# TheSixthSense.net
KiCad netlist of a schematic drawn in EAGLE
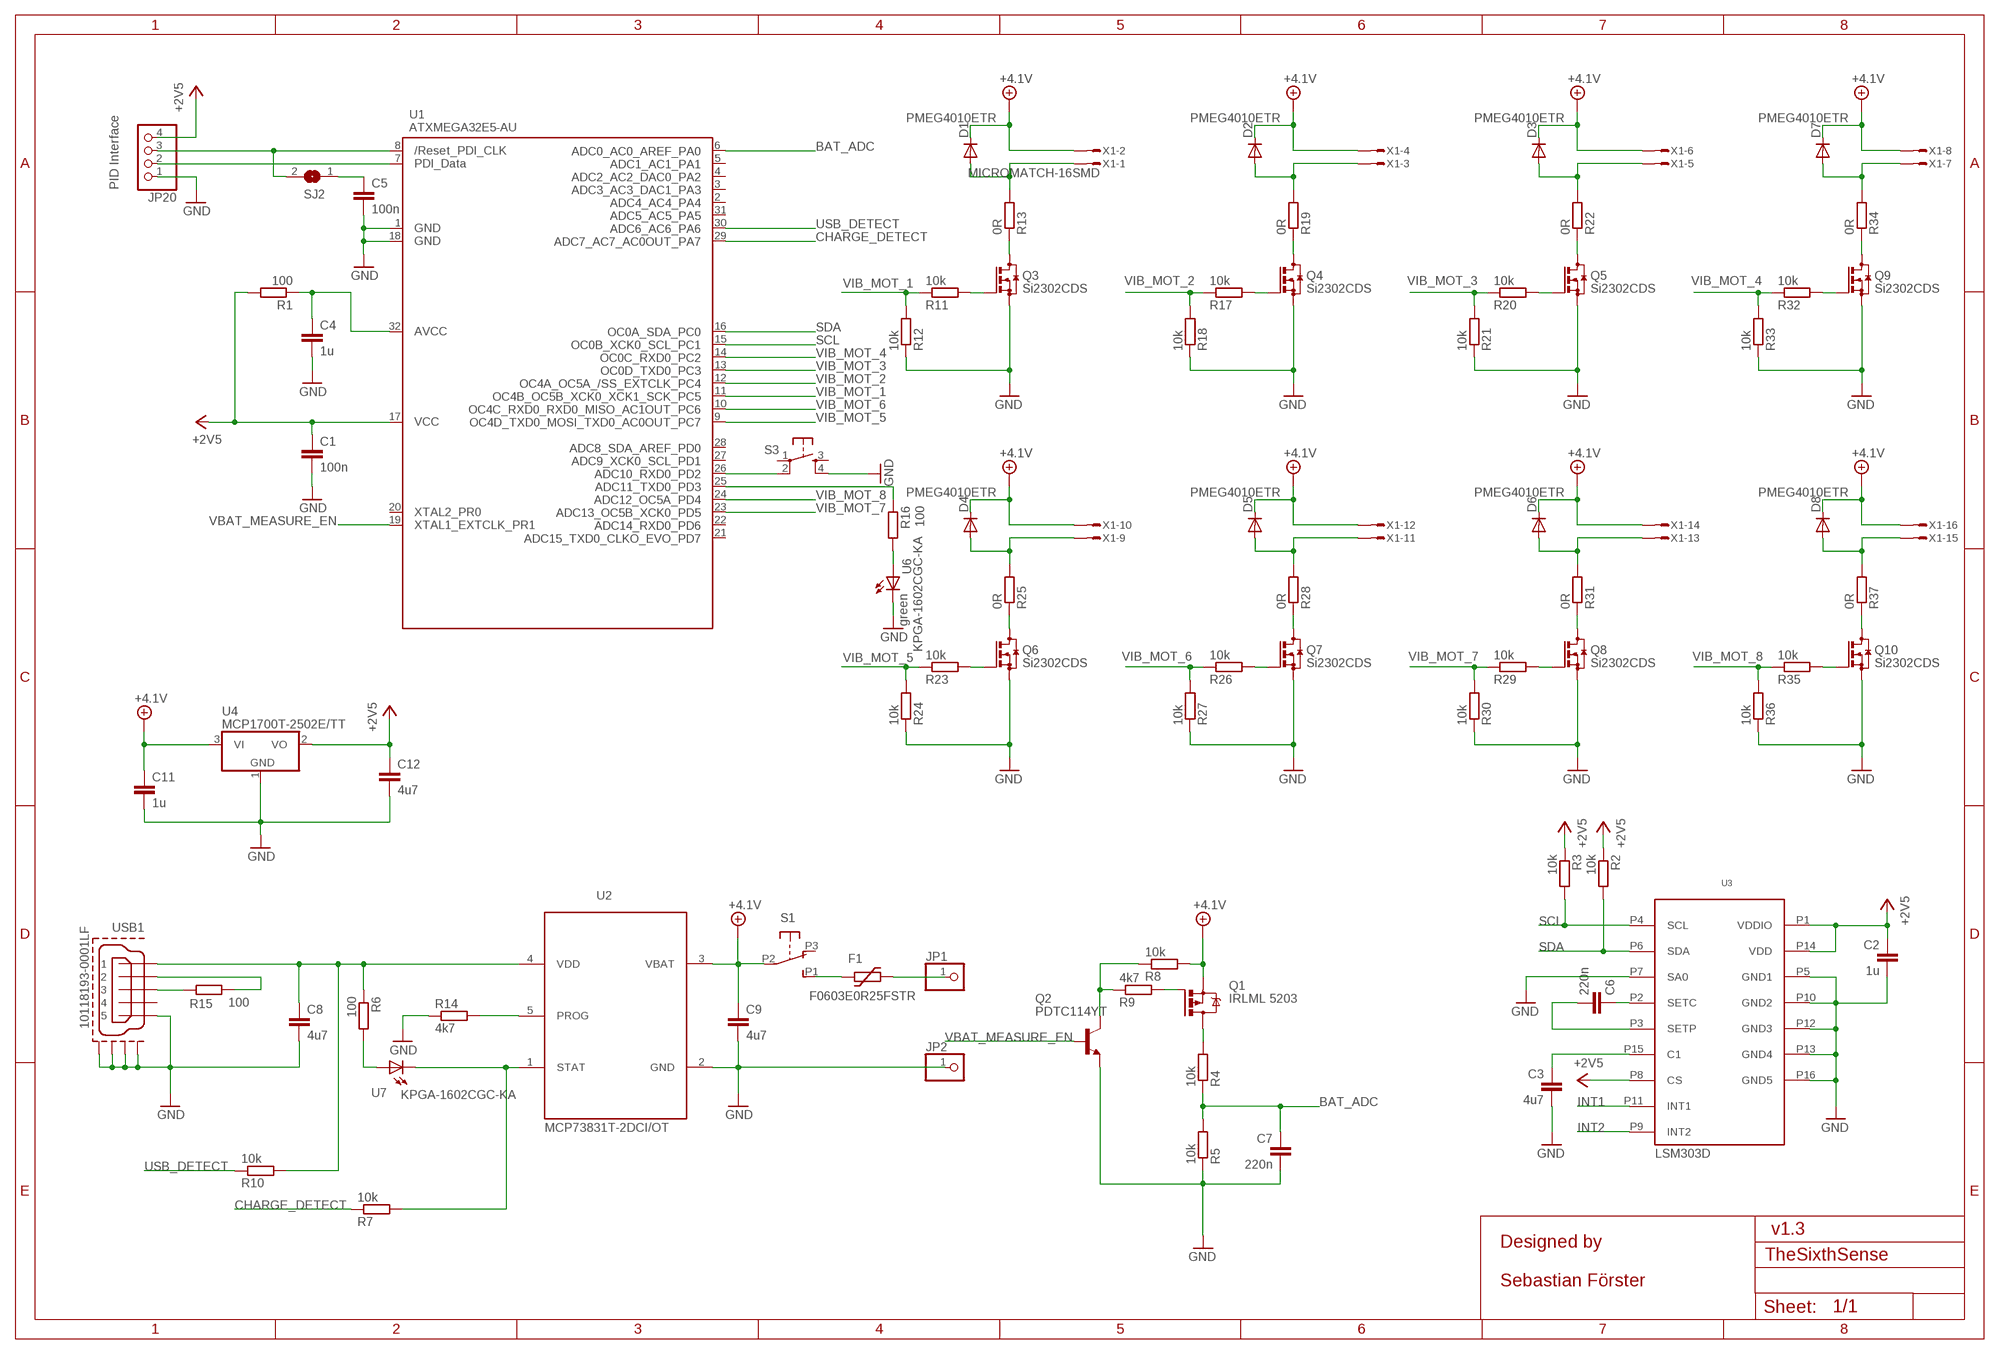
[diagram p0: schematic, sheet 1]

(export (version "E")
  (design (tool "Eeschema 10.0.6"))
  (components
    (comp (ref "C1")
      (value "100n")
      (footprint "eagle-import:C0603")
      (libsource (lib "eagle-import") (part "C-EUC0603"))
    )
    (comp (ref "C2")
      (value "1u")
      (footprint "eagle-import:C0603")
      (libsource (lib "eagle-import") (part "C-EUC0603"))
    )
    (comp (ref "C3")
      (value "4u7")
      (footprint "eagle-import:C0603")
      (libsource (lib "eagle-import") (part "C-EUC0603"))
    )
    (comp (ref "C4")
      (value "1u")
      (footprint "eagle-import:C0603")
      (libsource (lib "eagle-import") (part "C-EUC0603"))
    )
    (comp (ref "C5")
      (value "100n")
      (footprint "eagle-import:C0603")
      (libsource (lib "eagle-import") (part "C-EUC0603"))
    )
    (comp (ref "C6")
      (value "220n")
      (footprint "eagle-import:C0603")
      (libsource (lib "eagle-import") (part "C-EUC0603"))
    )
    (comp (ref "C7")
      (value "220n")
      (footprint "eagle-import:C0603")
      (libsource (lib "eagle-import") (part "C-EUC0603"))
    )
    (comp (ref "C8")
      (value "4u7")
      (footprint "eagle-import:C0603")
      (libsource (lib "eagle-import") (part "C-EUC0603"))
    )
    (comp (ref "C9")
      (value "4u7")
      (footprint "eagle-import:C0603")
      (libsource (lib "eagle-import") (part "C-EUC0603"))
    )
    (comp (ref "C11")
      (value "1u")
      (footprint "eagle-import:C0603")
      (libsource (lib "eagle-import") (part "C-EUC0603"))
    )
    (comp (ref "C12")
      (value "4u7")
      (footprint "eagle-import:C0603")
      (libsource (lib "eagle-import") (part "C-EUC0603"))
    )
    (comp (ref "D1")
      (value "PMEG4010ETR")
      (footprint "eagle-import:SOD123")
      (libsource (lib "eagle-import") (part "MBR0520LT"))
    )
    (comp (ref "D2")
      (value "PMEG4010ETR")
      (footprint "eagle-import:SOD123")
      (libsource (lib "eagle-import") (part "MBR0520LT"))
    )
    (comp (ref "D3")
      (value "PMEG4010ETR")
      (footprint "eagle-import:SOD123")
      (libsource (lib "eagle-import") (part "MBR0520LT"))
    )
    (comp (ref "D4")
      (value "PMEG4010ETR")
      (footprint "eagle-import:SOD123")
      (libsource (lib "eagle-import") (part "MBR0520LT"))
    )
    (comp (ref "D5")
      (value "PMEG4010ETR")
      (footprint "eagle-import:SOD123")
      (libsource (lib "eagle-import") (part "MBR0520LT"))
    )
    (comp (ref "D6")
      (value "PMEG4010ETR")
      (footprint "eagle-import:SOD123")
      (libsource (lib "eagle-import") (part "MBR0520LT"))
    )
    (comp (ref "D7")
      (value "PMEG4010ETR")
      (footprint "eagle-import:SOD123")
      (libsource (lib "eagle-import") (part "MBR0520LT"))
    )
    (comp (ref "D8")
      (value "PMEG4010ETR")
      (footprint "eagle-import:SOD123")
      (libsource (lib "eagle-import") (part "MBR0520LT"))
    )
    (comp (ref "F1")
      (value "F0603E0R25FSTR")
      (footprint "eagle-import:R0603")
      (libsource (lib "eagle-import") (part "PMS1812"))
    )
    (comp (ref "JP1")
      (value "PINHD-1X1")
      (footprint "eagle-import:1X01")
      (libsource (lib "eagle-import") (part "PINHD-1X1"))
    )
    (comp (ref "JP2")
      (value "PINHD-1X1")
      (footprint "eagle-import:1X01")
      (libsource (lib "eagle-import") (part "PINHD-1X1"))
    )
    (comp (ref "JP20")
      (value "PINHD-1X4_2.00")
      (footprint "eagle-import:1X04M")
      (libsource (lib "eagle-import") (part "PINHD-1X4_2.00"))
    )
    (comp (ref "Q1")
      (value "IRLML 5203")
      (footprint "eagle-import:MICRO3")
      (libsource (lib "eagle-import") (part "IRLML5203"))
    )
    (comp (ref "Q2")
      (value "PDTC114YT")
      (footprint "eagle-import:SOT23")
      (libsource (lib "eagle-import") (part "BC848SMDALT1"))
    )
    (comp (ref "Q3")
      (value "Si2302CDS")
      (footprint "eagle-import:SOT23")
      (libsource (lib "eagle-import") (part "BSS123"))
    )
    (comp (ref "Q4")
      (value "Si2302CDS")
      (footprint "eagle-import:SOT23")
      (libsource (lib "eagle-import") (part "BSS123"))
    )
    (comp (ref "Q5")
      (value "Si2302CDS")
      (footprint "eagle-import:SOT23")
      (libsource (lib "eagle-import") (part "BSS123"))
    )
    (comp (ref "Q6")
      (value "Si2302CDS")
      (footprint "eagle-import:SOT23")
      (libsource (lib "eagle-import") (part "BSS123"))
    )
    (comp (ref "Q7")
      (value "Si2302CDS")
      (footprint "eagle-import:SOT23")
      (libsource (lib "eagle-import") (part "BSS123"))
    )
    (comp (ref "Q8")
      (value "Si2302CDS")
      (footprint "eagle-import:SOT23")
      (libsource (lib "eagle-import") (part "BSS123"))
    )
    (comp (ref "Q9")
      (value "Si2302CDS")
      (footprint "eagle-import:SOT23")
      (libsource (lib "eagle-import") (part "BSS123"))
    )
    (comp (ref "Q10")
      (value "Si2302CDS")
      (footprint "eagle-import:SOT23")
      (libsource (lib "eagle-import") (part "BSS123"))
    )
    (comp (ref "R1")
      (value "100")
      (footprint "eagle-import:R0603")
      (libsource (lib "eagle-import") (part "R-EU_R0603"))
    )
    (comp (ref "R2")
      (value "10k")
      (footprint "eagle-import:R0603")
      (libsource (lib "eagle-import") (part "R-EU_R0603"))
    )
    (comp (ref "R3")
      (value "10k")
      (footprint "eagle-import:R0603")
      (libsource (lib "eagle-import") (part "R-EU_R0603"))
    )
    (comp (ref "R4")
      (value "10k")
      (footprint "eagle-import:R0603")
      (libsource (lib "eagle-import") (part "R-EU_R0603"))
    )
    (comp (ref "R5")
      (value "10k")
      (footprint "eagle-import:R0603")
      (libsource (lib "eagle-import") (part "R-EU_R0603"))
    )
    (comp (ref "R6")
      (value "100")
      (footprint "eagle-import:R0603")
      (libsource (lib "eagle-import") (part "R-EU_R0603"))
    )
    (comp (ref "R7")
      (value "10k")
      (footprint "eagle-import:R0603")
      (libsource (lib "eagle-import") (part "R-EU_R0603"))
    )
    (comp (ref "R8")
      (value "10k")
      (footprint "eagle-import:R0603")
      (libsource (lib "eagle-import") (part "R-EU_R0603"))
    )
    (comp (ref "R9")
      (value "4k7")
      (footprint "eagle-import:R0603")
      (libsource (lib "eagle-import") (part "R-EU_R0603"))
    )
    (comp (ref "R10")
      (value "10k")
      (footprint "eagle-import:R0603")
      (libsource (lib "eagle-import") (part "R-EU_R0603"))
    )
    (comp (ref "R11")
      (value "10k")
      (footprint "eagle-import:R0603")
      (libsource (lib "eagle-import") (part "R-EU_R0603"))
    )
    (comp (ref "R12")
      (value "10k")
      (footprint "eagle-import:R0603")
      (libsource (lib "eagle-import") (part "R-EU_R0603"))
    )
    (comp (ref "R13")
      (value "0R")
      (footprint "eagle-import:R0603")
      (libsource (lib "eagle-import") (part "R-EU_R0603"))
    )
    (comp (ref "R14")
      (value "4k7")
      (footprint "eagle-import:R0603")
      (libsource (lib "eagle-import") (part "R-EU_R0603"))
    )
    (comp (ref "R15")
      (value "100")
      (footprint "eagle-import:R0603")
      (libsource (lib "eagle-import") (part "R-EU_R0603"))
    )
    (comp (ref "R16")
      (value "100")
      (footprint "eagle-import:R0603")
      (libsource (lib "eagle-import") (part "R-EU_R0603"))
    )
    (comp (ref "R17")
      (value "10k")
      (footprint "eagle-import:R0603")
      (libsource (lib "eagle-import") (part "R-EU_R0603"))
    )
    (comp (ref "R18")
      (value "10k")
      (footprint "eagle-import:R0603")
      (libsource (lib "eagle-import") (part "R-EU_R0603"))
    )
    (comp (ref "R19")
      (value "0R")
      (footprint "eagle-import:R0603")
      (libsource (lib "eagle-import") (part "R-EU_R0603"))
    )
    (comp (ref "R20")
      (value "10k")
      (footprint "eagle-import:R0603")
      (libsource (lib "eagle-import") (part "R-EU_R0603"))
    )
    (comp (ref "R21")
      (value "10k")
      (footprint "eagle-import:R0603")
      (libsource (lib "eagle-import") (part "R-EU_R0603"))
    )
    (comp (ref "R22")
      (value "0R")
      (footprint "eagle-import:R0603")
      (libsource (lib "eagle-import") (part "R-EU_R0603"))
    )
    (comp (ref "R23")
      (value "10k")
      (footprint "eagle-import:R0603")
      (libsource (lib "eagle-import") (part "R-EU_R0603"))
    )
    (comp (ref "R24")
      (value "10k")
      (footprint "eagle-import:R0603")
      (libsource (lib "eagle-import") (part "R-EU_R0603"))
    )
    (comp (ref "R25")
      (value "0R")
      (footprint "eagle-import:R0603")
      (libsource (lib "eagle-import") (part "R-EU_R0603"))
    )
    (comp (ref "R26")
      (value "10k")
      (footprint "eagle-import:R0603")
      (libsource (lib "eagle-import") (part "R-EU_R0603"))
    )
    (comp (ref "R27")
      (value "10k")
      (footprint "eagle-import:R0603")
      (libsource (lib "eagle-import") (part "R-EU_R0603"))
    )
    (comp (ref "R28")
      (value "0R")
      (footprint "eagle-import:R0603")
      (libsource (lib "eagle-import") (part "R-EU_R0603"))
    )
    (comp (ref "R29")
      (value "10k")
      (footprint "eagle-import:R0603")
      (libsource (lib "eagle-import") (part "R-EU_R0603"))
    )
    (comp (ref "R30")
      (value "10k")
      (footprint "eagle-import:R0603")
      (libsource (lib "eagle-import") (part "R-EU_R0603"))
    )
    (comp (ref "R31")
      (value "0R")
      (footprint "eagle-import:R0603")
      (libsource (lib "eagle-import") (part "R-EU_R0603"))
    )
    (comp (ref "R32")
      (value "10k")
      (footprint "eagle-import:R0603")
      (libsource (lib "eagle-import") (part "R-EU_R0603"))
    )
    (comp (ref "R33")
      (value "10k")
      (footprint "eagle-import:R0603")
      (libsource (lib "eagle-import") (part "R-EU_R0603"))
    )
    (comp (ref "R34")
      (value "0R")
      (footprint "eagle-import:R0603")
      (libsource (lib "eagle-import") (part "R-EU_R0603"))
    )
    (comp (ref "R35")
      (value "10k")
      (footprint "eagle-import:R0603")
      (libsource (lib "eagle-import") (part "R-EU_R0603"))
    )
    (comp (ref "R36")
      (value "10k")
      (footprint "eagle-import:R0603")
      (libsource (lib "eagle-import") (part "R-EU_R0603"))
    )
    (comp (ref "R37")
      (value "0R")
      (footprint "eagle-import:R0603")
      (libsource (lib "eagle-import") (part "R-EU_R0603"))
    )
    (comp (ref "S1")
      (value "ALPSSSSS811101")
      (footprint "eagle-import:SSSS811101")
      (libsource (lib "eagle-import") (part "ALPSSSSS811101"))
    )
    (comp (ref "S3")
      (value "10-XX")
      (footprint "eagle-import:SKSCLAE010")
      (libsource (lib "eagle-import") (part "10-XX"))
    )
    (comp (ref "SJ2") (value "SJ") (footprint "eagle-import:SJ") (libsource (lib "eagle-import") (part "SJ")))
    (comp (ref "U1")
      (value "ATXMEGA32E5-AU")
      (footprint "eagle-import:TQFP32-08")
      (libsource (lib "eagle-import") (part "AVR_XMEGA_E"))
    )
    (comp (ref "U2")
      (value "MCP73831")
      (footprint "eagle-import:SOT23-5L")
      (libsource (lib "eagle-import") (part "MCP73831"))
    )
    (comp (ref "U3")
      (value "LSM303D")
      (footprint "eagle-import:LGA3X3_16L")
      (libsource (lib "eagle-import") (part "LSM303D"))
    )
    (comp (ref "U4")
      (value "MCP1700T-2502E/TT")
      (footprint "eagle-import:SOT23")
      (libsource (lib "eagle-import") (part "XC6206P332MR"))
    )
    (comp (ref "U6")
      (value "KPGA-1602CGC-KA")
      (footprint "eagle-import:CHIP-LED0603")
      (libsource (lib "eagle-import") (part "APA1606SURCK"))
    )
    (comp (ref "U7")
      (value "KPGA-1602CGC-KA")
      (footprint "eagle-import:CHIP-LED0603")
      (libsource (lib "eagle-import") (part "APA1606SURCK"))
    )
    (comp (ref "USB1")
      (value "10118193-0001LF")
      (footprint "eagle-import:MOLEX-47364-0001")
      (libsource (lib "eagle-import") (part "MOLEX-47346-0001"))
    )
    (comp (ref "X1")
      (value "MICROMATCH-16SMD")
      (footprint "eagle-import:MICROMATCH-16SMD")
      (libsource (lib "eagle-import") (part "MICROMATCH-16SMD"))
    )
  )
  (nets
    (net (code "1") (name "+2V5") (class "Default")
      (node (ref "C1") (pin "1") (pinfunction "1_1") (pintype "passive"))
      (node (ref "C12") (pin "1") (pinfunction "1_1") (pintype "passive"))
      (node (ref "C2") (pin "1") (pinfunction "1_1") (pintype "passive"))
      (node (ref "JP20") (pin "4") (pinfunction "4_4") (pintype "passive"))
      (node (ref "R1") (pin "2") (pinfunction "2_2") (pintype "passive"))
      (node (ref "R2") (pin "1") (pinfunction "1_1") (pintype "passive"))
      (node (ref "R3") (pin "1") (pinfunction "1_1") (pintype "passive"))
      (node (ref "U1") (pin "17") (pinfunction "VCC3_17") (pintype "bidirectional"))
      (node (ref "U3") (pin "P1") (pinfunction "VDDIO_P1") (pintype "bidirectional"))
      (node (ref "U3") (pin "P14") (pinfunction "VDD_P14") (pintype "bidirectional"))
      (node (ref "U3") (pin "P8") (pinfunction "CS_P8") (pintype "bidirectional"))
      (node (ref "U4") (pin "2") (pinfunction "VO_2") (pintype "passive"))
    )
    (net (code "2") (name "+4.1V") (class "Default")
      (node (ref "C11") (pin "1") (pinfunction "1_1") (pintype "passive"))
      (node (ref "C9") (pin "1") (pinfunction "1_1") (pintype "passive"))
      (node (ref "D1") (pin "C") (pinfunction "C_C") (pintype "passive"))
      (node (ref "D2") (pin "C") (pinfunction "C_C") (pintype "passive"))
      (node (ref "D3") (pin "C") (pinfunction "C_C") (pintype "passive"))
      (node (ref "D4") (pin "C") (pinfunction "C_C") (pintype "passive"))
      (node (ref "D5") (pin "C") (pinfunction "C_C") (pintype "passive"))
      (node (ref "D6") (pin "C") (pinfunction "C_C") (pintype "passive"))
      (node (ref "D7") (pin "C") (pinfunction "C_C") (pintype "passive"))
      (node (ref "D8") (pin "C") (pinfunction "C_C") (pintype "passive"))
      (node (ref "Q1") (pin "2") (pinfunction "S_2") (pintype "passive"))
      (node (ref "R8") (pin "2") (pinfunction "2_2") (pintype "passive"))
      (node (ref "S1") (pin "P2") (pinfunction "P_P2") (pintype "passive"))
      (node (ref "U2") (pin "3") (pinfunction "VBAT_3") (pintype "bidirectional"))
      (node (ref "U4") (pin "3") (pinfunction "VI_3") (pintype "input"))
      (node (ref "X1") (pin "1") (pinfunction "S_1") (pintype "passive"))
      (node (ref "X1") (pin "11") (pinfunction "S_11") (pintype "passive"))
      (node (ref "X1") (pin "13") (pinfunction "S_13") (pintype "passive"))
      (node (ref "X1") (pin "15") (pinfunction "S_15") (pintype "passive"))
      (node (ref "X1") (pin "3") (pinfunction "S_3") (pintype "passive"))
      (node (ref "X1") (pin "5") (pinfunction "S_5") (pintype "passive"))
      (node (ref "X1") (pin "7") (pinfunction "S_7") (pintype "passive"))
      (node (ref "X1") (pin "9") (pinfunction "S_9") (pintype "passive"))
    )
    (net (code "3") (name "/BAT_ADC") (class "Default")
      (node (ref "C7") (pin "1") (pinfunction "1_1") (pintype "passive"))
      (node (ref "R4") (pin "1") (pinfunction "1_1") (pintype "passive"))
      (node (ref "R5") (pin "2") (pinfunction "2_2") (pintype "passive"))
      (node (ref "U1") (pin "6") (pinfunction "PA0_6") (pintype "bidirectional"))
    )
    (net (code "4") (name "/CHARGE_DETECT") (class "Default")
      (node (ref "R7") (pin "1") (pinfunction "1_1") (pintype "passive"))
      (node (ref "U1") (pin "29") (pinfunction "PA7_29") (pintype "bidirectional"))
    )
    (net (code "5") (name "/INT1") (class "Default")
      (node (ref "U3") (pin "P11") (pinfunction "INT1_P11") (pintype "bidirectional"))
    )
    (net (code "6") (name "/INT2") (class "Default")
      (node (ref "U3") (pin "P9") (pinfunction "INT2_P9") (pintype "bidirectional"))
    )
    (net (code "7") (name "/SCL") (class "Default")
      (node (ref "R3") (pin "2") (pinfunction "2_2") (pintype "passive"))
      (node (ref "U1") (pin "15") (pinfunction "PC1_15") (pintype "bidirectional"))
      (node (ref "U3") (pin "P4") (pinfunction "SCL_P4") (pintype "bidirectional"))
    )
    (net (code "8") (name "/SDA") (class "Default")
      (node (ref "R2") (pin "2") (pinfunction "2_2") (pintype "passive"))
      (node (ref "U1") (pin "16") (pinfunction "PC0_16") (pintype "bidirectional"))
      (node (ref "U3") (pin "P6") (pinfunction "SDA_P6") (pintype "bidirectional"))
    )
    (net (code "9") (name "/USB_DETECT") (class "Default")
      (node (ref "R10") (pin "1") (pinfunction "1_1") (pintype "passive"))
      (node (ref "U1") (pin "30") (pinfunction "PA6_30") (pintype "bidirectional"))
    )
    (net (code "10") (name "/VBAT_MEASURE_EN") (class "Default")
      (node (ref "Q2") (pin "1") (pinfunction "B_1") (pintype "passive"))
      (node (ref "U1") (pin "19") (pinfunction "PR1_19") (pintype "bidirectional"))
    )
    (net (code "11") (name "/VIB_MOT_1") (class "Default")
      (node (ref "R11") (pin "1") (pinfunction "1_1") (pintype "passive"))
      (node (ref "R12") (pin "2") (pinfunction "2_2") (pintype "passive"))
      (node (ref "U1") (pin "11") (pinfunction "PC5_11") (pintype "bidirectional"))
    )
    (net (code "12") (name "/VIB_MOT_2") (class "Default")
      (node (ref "R17") (pin "1") (pinfunction "1_1") (pintype "passive"))
      (node (ref "R18") (pin "2") (pinfunction "2_2") (pintype "passive"))
      (node (ref "U1") (pin "12") (pinfunction "PC4_12") (pintype "bidirectional"))
    )
    (net (code "13") (name "/VIB_MOT_3") (class "Default")
      (node (ref "R20") (pin "1") (pinfunction "1_1") (pintype "passive"))
      (node (ref "R21") (pin "2") (pinfunction "2_2") (pintype "passive"))
      (node (ref "U1") (pin "13") (pinfunction "PC3_13") (pintype "bidirectional"))
    )
    (net (code "14") (name "/VIB_MOT_4") (class "Default")
      (node (ref "R32") (pin "1") (pinfunction "1_1") (pintype "passive"))
      (node (ref "R33") (pin "2") (pinfunction "2_2") (pintype "passive"))
      (node (ref "U1") (pin "14") (pinfunction "PC2_14") (pintype "bidirectional"))
    )
    (net (code "15") (name "/VIB_MOT_5") (class "Default")
      (node (ref "R23") (pin "1") (pinfunction "1_1") (pintype "passive"))
      (node (ref "R24") (pin "2") (pinfunction "2_2") (pintype "passive"))
      (node (ref "U1") (pin "9") (pinfunction "PC7_9") (pintype "bidirectional"))
    )
    (net (code "16") (name "/VIB_MOT_6") (class "Default")
      (node (ref "R26") (pin "1") (pinfunction "1_1") (pintype "passive"))
      (node (ref "R27") (pin "2") (pinfunction "2_2") (pintype "passive"))
      (node (ref "U1") (pin "10") (pinfunction "PC6_10") (pintype "bidirectional"))
    )
    (net (code "17") (name "/VIB_MOT_7") (class "Default")
      (node (ref "R29") (pin "1") (pinfunction "1_1") (pintype "passive"))
      (node (ref "R30") (pin "2") (pinfunction "2_2") (pintype "passive"))
      (node (ref "U1") (pin "23") (pinfunction "PD5_23") (pintype "bidirectional"))
    )
    (net (code "18") (name "/VIB_MOT_8") (class "Default")
      (node (ref "R35") (pin "1") (pinfunction "1_1") (pintype "passive"))
      (node (ref "R36") (pin "2") (pinfunction "2_2") (pintype "passive"))
      (node (ref "U1") (pin "24") (pinfunction "PD4_24") (pintype "bidirectional"))
    )
    (net (code "19") (name "GND") (class "Default")
      (node (ref "C1") (pin "2") (pinfunction "2_2") (pintype "passive"))
      (node (ref "C11") (pin "2") (pinfunction "2_2") (pintype "passive"))
      (node (ref "C12") (pin "2") (pinfunction "2_2") (pintype "passive"))
      (node (ref "C2") (pin "2") (pinfunction "2_2") (pintype "passive"))
      (node (ref "C3") (pin "2") (pinfunction "2_2") (pintype "passive"))
      (node (ref "C4") (pin "2") (pinfunction "2_2") (pintype "passive"))
      (node (ref "C5") (pin "2") (pinfunction "2_2") (pintype "passive"))
      (node (ref "C7") (pin "2") (pinfunction "2_2") (pintype "passive"))
      (node (ref "C8") (pin "2") (pinfunction "2_2") (pintype "passive"))
      (node (ref "C9") (pin "2") (pinfunction "2_2") (pintype "passive"))
      (node (ref "JP2") (pin "1") (pinfunction "1_1") (pintype "passive"))
      (node (ref "JP20") (pin "1") (pinfunction "1_1") (pintype "passive"))
      (node (ref "Q10") (pin "2") (pinfunction "S_2") (pintype "passive"))
      (node (ref "Q2") (pin "2") (pinfunction "E_2") (pintype "passive"))
      (node (ref "Q3") (pin "2") (pinfunction "S_2") (pintype "passive"))
      (node (ref "Q4") (pin "2") (pinfunction "S_2") (pintype "passive"))
      (node (ref "Q5") (pin "2") (pinfunction "S_2") (pintype "passive"))
      (node (ref "Q6") (pin "2") (pinfunction "S_2") (pintype "passive"))
      (node (ref "Q7") (pin "2") (pinfunction "S_2") (pintype "passive"))
      (node (ref "Q8") (pin "2") (pinfunction "S_2") (pintype "passive"))
      (node (ref "Q9") (pin "2") (pinfunction "S_2") (pintype "passive"))
      (node (ref "R12") (pin "1") (pinfunction "1_1") (pintype "passive"))
      (node (ref "R14") (pin "1") (pinfunction "1_1") (pintype "passive"))
      (node (ref "R18") (pin "1") (pinfunction "1_1") (pintype "passive"))
      (node (ref "R21") (pin "1") (pinfunction "1_1") (pintype "passive"))
      (node (ref "R24") (pin "1") (pinfunction "1_1") (pintype "passive"))
      (node (ref "R27") (pin "1") (pinfunction "1_1") (pintype "passive"))
      (node (ref "R30") (pin "1") (pinfunction "1_1") (pintype "passive"))
      (node (ref "R33") (pin "1") (pinfunction "1_1") (pintype "passive"))
      (node (ref "R36") (pin "1") (pinfunction "1_1") (pintype "passive"))
      (node (ref "R5") (pin "1") (pinfunction "1_1") (pintype "passive"))
      (node (ref "S3") (pin "4") (pinfunction "S1_4") (pintype "passive"))
      (node (ref "U1") (pin "1") (pinfunction "GND1_1") (pintype "bidirectional"))
      (node (ref "U1") (pin "18") (pinfunction "GND2_18") (pintype "bidirectional"))
      (node (ref "U2") (pin "2") (pinfunction "GND_2") (pintype "bidirectional"))
      (node (ref "U3") (pin "P10") (pinfunction "GND2_P10") (pintype "bidirectional"))
      (node (ref "U3") (pin "P12") (pinfunction "GND3_P12") (pintype "bidirectional"))
      (node (ref "U3") (pin "P13") (pinfunction "GND4_P13") (pintype "bidirectional"))
      (node (ref "U3") (pin "P16") (pinfunction "GND5_P16") (pintype "bidirectional"))
      (node (ref "U3") (pin "P5") (pinfunction "GND1_P5") (pintype "bidirectional"))
      (node (ref "U3") (pin "P7") (pinfunction "SA0_P7") (pintype "bidirectional"))
      (node (ref "U4") (pin "1") (pinfunction "GND_1") (pintype "passive"))
      (node (ref "U6") (pin "C") (pinfunction "C_C") (pintype "passive"))
      (node (ref "USB1") (pin "5") (pinfunction "5_5") (pintype "input"))
      (node (ref "USB1") (pin "GND1") (pinfunction "GND1_GND1") (pintype "bidirectional"))
      (node (ref "USB1") (pin "GND2") (pinfunction "GND2_GND2") (pintype "bidirectional"))
      (node (ref "USB1") (pin "GND3") (pinfunction "GND3_GND3") (pintype "bidirectional"))
      (node (ref "USB1") (pin "GND4") (pinfunction "GND4_GND4") (pintype "bidirectional"))
    )
    (net (code "20") (name "Net-(C5-Pad1)") (class "Default")
      (node (ref "C5") (pin "1") (pinfunction "1_1") (pintype "passive"))
      (node (ref "SJ2") (pin "1") (pinfunction "1_1") (pintype "passive"))
    )
    (net (code "21") (name "Net-(F1-Pad2)") (class "Default")
      (node (ref "F1") (pin "2") (pinfunction "2_2") (pintype "passive"))
      (node (ref "JP1") (pin "1") (pinfunction "1_1") (pintype "passive"))
    )
    (net (code "22") (name "Net-(Q1-D)") (class "Default")
      (node (ref "Q1") (pin "3") (pinfunction "D_3") (pintype "passive"))
      (node (ref "R4") (pin "2") (pinfunction "2_2") (pintype "passive"))
    )
    (net (code "23") (name "Net-(Q1-G)") (class "Default")
      (node (ref "Q1") (pin "1") (pinfunction "G_1") (pintype "passive"))
      (node (ref "R9") (pin "2") (pinfunction "2_2") (pintype "passive"))
    )
    (net (code "24") (name "Net-(Q2-C)") (class "Default")
      (node (ref "Q2") (pin "3") (pinfunction "C_3") (pintype "passive"))
      (node (ref "R8") (pin "1") (pinfunction "1_1") (pintype "passive"))
      (node (ref "R9") (pin "1") (pinfunction "1_1") (pintype "passive"))
    )
    (net (code "25") (name "Net-(Q3-D)") (class "Default")
      (node (ref "Q3") (pin "3") (pinfunction "D_3") (pintype "passive"))
      (node (ref "R13") (pin "1") (pinfunction "1_1") (pintype "passive"))
    )
    (net (code "26") (name "Net-(Q3-G)") (class "Default")
      (node (ref "Q3") (pin "1") (pinfunction "G_1") (pintype "passive"))
      (node (ref "R11") (pin "2") (pinfunction "2_2") (pintype "passive"))
    )
    (net (code "27") (name "Net-(Q4-D)") (class "Default")
      (node (ref "Q4") (pin "3") (pinfunction "D_3") (pintype "passive"))
      (node (ref "R19") (pin "1") (pinfunction "1_1") (pintype "passive"))
    )
    (net (code "28") (name "Net-(Q4-G)") (class "Default")
      (node (ref "Q4") (pin "1") (pinfunction "G_1") (pintype "passive"))
      (node (ref "R17") (pin "2") (pinfunction "2_2") (pintype "passive"))
    )
    (net (code "29") (name "Net-(Q5-D)") (class "Default")
      (node (ref "Q5") (pin "3") (pinfunction "D_3") (pintype "passive"))
      (node (ref "R22") (pin "1") (pinfunction "1_1") (pintype "passive"))
    )
    (net (code "30") (name "Net-(Q5-G)") (class "Default")
      (node (ref "Q5") (pin "1") (pinfunction "G_1") (pintype "passive"))
      (node (ref "R20") (pin "2") (pinfunction "2_2") (pintype "passive"))
    )
    (net (code "31") (name "Net-(Q6-D)") (class "Default")
      (node (ref "Q6") (pin "3") (pinfunction "D_3") (pintype "passive"))
      (node (ref "R25") (pin "1") (pinfunction "1_1") (pintype "passive"))
    )
    (net (code "32") (name "Net-(Q6-G)") (class "Default")
      (node (ref "Q6") (pin "1") (pinfunction "G_1") (pintype "passive"))
      (node (ref "R23") (pin "2") (pinfunction "2_2") (pintype "passive"))
    )
    (net (code "33") (name "Net-(Q7-D)") (class "Default")
      (node (ref "Q7") (pin "3") (pinfunction "D_3") (pintype "passive"))
      (node (ref "R28") (pin "1") (pinfunction "1_1") (pintype "passive"))
    )
    (net (code "34") (name "Net-(Q7-G)") (class "Default")
      (node (ref "Q7") (pin "1") (pinfunction "G_1") (pintype "passive"))
      (node (ref "R26") (pin "2") (pinfunction "2_2") (pintype "passive"))
    )
    (net (code "35") (name "Net-(Q8-D)") (class "Default")
      (node (ref "Q8") (pin "3") (pinfunction "D_3") (pintype "passive"))
      (node (ref "R31") (pin "1") (pinfunction "1_1") (pintype "passive"))
    )
    (net (code "36") (name "Net-(Q8-G)") (class "Default")
      (node (ref "Q8") (pin "1") (pinfunction "G_1") (pintype "passive"))
      (node (ref "R29") (pin "2") (pinfunction "2_2") (pintype "passive"))
    )
    (net (code "37") (name "Net-(Q9-D)") (class "Default")
      (node (ref "Q9") (pin "3") (pinfunction "D_3") (pintype "passive"))
      (node (ref "R34") (pin "1") (pinfunction "1_1") (pintype "passive"))
    )
    (net (code "38") (name "Net-(Q9-G)") (class "Default")
      (node (ref "Q9") (pin "1") (pinfunction "G_1") (pintype "passive"))
      (node (ref "R32") (pin "2") (pinfunction "2_2") (pintype "passive"))
    )
    (net (code "39") (name "Net-(Q10-D)") (class "Default")
      (node (ref "Q10") (pin "3") (pinfunction "D_3") (pintype "passive"))
      (node (ref "R37") (pin "1") (pinfunction "1_1") (pintype "passive"))
    )
    (net (code "40") (name "Net-(Q10-G)") (class "Default")
      (node (ref "Q10") (pin "1") (pinfunction "G_1") (pintype "passive"))
      (node (ref "R35") (pin "2") (pinfunction "2_2") (pintype "passive"))
    )
    (net (code "41") (name "Net-(R6-Pad2)") (class "Default")
      (node (ref "R6") (pin "2") (pinfunction "2_2") (pintype "passive"))
      (node (ref "U7") (pin "A") (pinfunction "A_A") (pintype "passive"))
    )
    (net (code "42") (name "Net-(R15-Pad1)") (class "Default")
      (node (ref "R15") (pin "1") (pinfunction "1_1") (pintype "passive"))
      (node (ref "USB1") (pin "3") (pinfunction "3_3") (pintype "input"))
    )
    (net (code "43") (name "Net-(R15-Pad2)") (class "Default")
      (node (ref "R15") (pin "2") (pinfunction "2_2") (pintype "passive"))
      (node (ref "USB1") (pin "2") (pinfunction "2_2") (pintype "input"))
    )
    (net (code "44") (name "Net-(R16-Pad2)") (class "Default")
      (node (ref "R16") (pin "2") (pinfunction "2_2") (pintype "passive"))
      (node (ref "U6") (pin "A") (pinfunction "A_A") (pintype "passive"))
    )
    (net (code "45") (name "Net-(S1-S)") (class "Default")
      (node (ref "F1") (pin "1") (pinfunction "1_1") (pintype "passive"))
      (node (ref "S1") (pin "P1") (pinfunction "S_P1") (pintype "passive"))
    )
    (net (code "46") (name "Net-(S3-P1)") (class "Default")
      (node (ref "S3") (pin "2") (pinfunction "P1_2") (pintype "passive"))
      (node (ref "U1") (pin "26") (pinfunction "PD2_26") (pintype "bidirectional"))
    )
    (net (code "47") (name "Net-(U1-AVCC)") (class "Default")
      (node (ref "C4") (pin "1") (pinfunction "1_1") (pintype "passive"))
      (node (ref "R1") (pin "1") (pinfunction "1_1") (pintype "passive"))
      (node (ref "U1") (pin "32") (pinfunction "AVCC_32") (pintype "bidirectional"))
    )
    (net (code "48") (name "Net-(U1-PD3)") (class "Default")
      (node (ref "R16") (pin "1") (pinfunction "1_1") (pintype "passive"))
      (node (ref "U1") (pin "25") (pinfunction "PD3_25") (pintype "bidirectional"))
    )
    (net (code "49") (name "Net-(U1-PDI_DATA)") (class "Default")
      (node (ref "JP20") (pin "2") (pinfunction "2_2") (pintype "passive"))
      (node (ref "U1") (pin "7") (pinfunction "PDI_DATA_7") (pintype "bidirectional"))
    )
    (net (code "50") (name "Net-(U1-RESET)") (class "Default")
      (node (ref "JP20") (pin "3") (pinfunction "3_3") (pintype "passive"))
      (node (ref "SJ2") (pin "2") (pinfunction "2_2") (pintype "passive"))
      (node (ref "U1") (pin "8") (pinfunction "RESET_8") (pintype "bidirectional"))
    )
    (net (code "51") (name "Net-(U2-PROG)") (class "Default")
      (node (ref "R14") (pin "2") (pinfunction "2_2") (pintype "passive"))
      (node (ref "U2") (pin "5") (pinfunction "PROG_5") (pintype "bidirectional"))
    )
    (net (code "52") (name "Net-(U2-STAT)") (class "Default")
      (node (ref "R7") (pin "2") (pinfunction "2_2") (pintype "passive"))
      (node (ref "U2") (pin "1") (pinfunction "STAT_1") (pintype "bidirectional"))
      (node (ref "U7") (pin "C") (pinfunction "C_C") (pintype "passive"))
    )
    (net (code "53") (name "Net-(U2-VDD)") (class "Default")
      (node (ref "C8") (pin "1") (pinfunction "1_1") (pintype "passive"))
      (node (ref "R10") (pin "2") (pinfunction "2_2") (pintype "passive"))
      (node (ref "R6") (pin "1") (pinfunction "1_1") (pintype "passive"))
      (node (ref "U2") (pin "4") (pinfunction "VDD_4") (pintype "bidirectional"))
      (node (ref "USB1") (pin "1") (pinfunction "1_1") (pintype "input"))
    )
    (net (code "54") (name "Net-(U3-C1)") (class "Default")
      (node (ref "C3") (pin "1") (pinfunction "1_1") (pintype "passive"))
      (node (ref "U3") (pin "P15") (pinfunction "C1_P15") (pintype "bidirectional"))
    )
    (net (code "55") (name "Net-(U3-SETC)") (class "Default")
      (node (ref "C6") (pin "1") (pinfunction "1_1") (pintype "passive"))
      (node (ref "U3") (pin "P2") (pinfunction "SETC_P2") (pintype "bidirectional"))
    )
    (net (code "56") (name "Net-(U3-SETP)") (class "Default")
      (node (ref "C6") (pin "2") (pinfunction "2_2") (pintype "passive"))
      (node (ref "U3") (pin "P3") (pinfunction "SETP_P3") (pintype "bidirectional"))
    )
    (net (code "57") (name "Net-(X1A-S)") (class "Default")
      (node (ref "D1") (pin "A") (pinfunction "A_A") (pintype "passive"))
      (node (ref "R13") (pin "2") (pinfunction "2_2") (pintype "passive"))
      (node (ref "X1") (pin "16") (pinfunction "S_16") (pintype "passive"))
    )
    (net (code "58") (name "Net-(X1C-S)") (class "Default")
      (node (ref "D5") (pin "A") (pinfunction "A_A") (pintype "passive"))
      (node (ref "R28") (pin "2") (pinfunction "2_2") (pintype "passive"))
      (node (ref "X1") (pin "6") (pinfunction "S_6") (pintype "passive"))
    )
    (net (code "59") (name "Net-(X1E-S)") (class "Default")
      (node (ref "D6") (pin "A") (pinfunction "A_A") (pintype "passive"))
      (node (ref "R31") (pin "2") (pinfunction "2_2") (pintype "passive"))
      (node (ref "X1") (pin "4") (pinfunction "S_4") (pintype "passive"))
    )
    (net (code "60") (name "Net-(X1G-S)") (class "Default")
      (node (ref "D8") (pin "A") (pinfunction "A_A") (pintype "passive"))
      (node (ref "R37") (pin "2") (pinfunction "2_2") (pintype "passive"))
      (node (ref "X1") (pin "2") (pinfunction "S_2") (pintype "passive"))
    )
    (net (code "61") (name "Net-(X1J-S)") (class "Default")
      (node (ref "D2") (pin "A") (pinfunction "A_A") (pintype "passive"))
      (node (ref "R19") (pin "2") (pinfunction "2_2") (pintype "passive"))
      (node (ref "X1") (pin "14") (pinfunction "S_14") (pintype "passive"))
    )
    (net (code "62") (name "Net-(X1L-S)") (class "Default")
      (node (ref "D3") (pin "A") (pinfunction "A_A") (pintype "passive"))
      (node (ref "R22") (pin "2") (pinfunction "2_2") (pintype "passive"))
      (node (ref "X1") (pin "12") (pinfunction "S_12") (pintype "passive"))
    )
    (net (code "63") (name "Net-(X1N-S)") (class "Default")
      (node (ref "D7") (pin "A") (pinfunction "A_A") (pintype "passive"))
      (node (ref "R34") (pin "2") (pinfunction "2_2") (pintype "passive"))
      (node (ref "X1") (pin "10") (pinfunction "S_10") (pintype "passive"))
    )
    (net (code "64") (name "Net-(X1P-S)") (class "Default")
      (node (ref "D4") (pin "A") (pinfunction "A_A") (pintype "passive"))
      (node (ref "R25") (pin "2") (pinfunction "2_2") (pintype "passive"))
      (node (ref "X1") (pin "8") (pinfunction "S_8") (pintype "passive"))
    )
    (net (code "65") (name "unconnected-(S1-O-PadP3)") (class "Default")
      (node (ref "S1") (pin "P3") (pinfunction "O_P3") (pintype "passive"))
    )
    (net (code "66") (name "unconnected-(S3-P-Pad1)") (class "Default")
      (node (ref "S3") (pin "1") (pinfunction "P_1") (pintype "passive"))
    )
    (net (code "67") (name "unconnected-(S3-S-Pad3)") (class "Default")
      (node (ref "S3") (pin "3") (pinfunction "S_3") (pintype "passive"))
    )
    (net (code "68") (name "unconnected-(U1-PA1-Pad5)") (class "Default")
      (node (ref "U1") (pin "5") (pinfunction "PA1_5") (pintype "bidirectional"))
    )
    (net (code "69") (name "unconnected-(U1-PA2-Pad4)") (class "Default")
      (node (ref "U1") (pin "4") (pinfunction "PA2_4") (pintype "bidirectional"))
    )
    (net (code "70") (name "unconnected-(U1-PA3-Pad3)") (class "Default")
      (node (ref "U1") (pin "3") (pinfunction "PA3_3") (pintype "bidirectional"))
    )
    (net (code "71") (name "unconnected-(U1-PA4-Pad2)") (class "Default")
      (node (ref "U1") (pin "2") (pinfunction "PA4_2") (pintype "bidirectional"))
    )
    (net (code "72") (name "unconnected-(U1-PA5-Pad31)") (class "Default")
      (node (ref "U1") (pin "31") (pinfunction "PA5_31") (pintype "bidirectional"))
    )
    (net (code "73") (name "unconnected-(U1-PD0-Pad28)") (class "Default")
      (node (ref "U1") (pin "28") (pinfunction "PD0_28") (pintype "bidirectional"))
    )
    (net (code "74") (name "unconnected-(U1-PD1-Pad27)") (class "Default")
      (node (ref "U1") (pin "27") (pinfunction "PD1_27") (pintype "bidirectional"))
    )
    (net (code "75") (name "unconnected-(U1-PD6-Pad22)") (class "Default")
      (node (ref "U1") (pin "22") (pinfunction "PD6_22") (pintype "bidirectional"))
    )
    (net (code "76") (name "unconnected-(U1-PD7-Pad21)") (class "Default")
      (node (ref "U1") (pin "21") (pinfunction "PD7_21") (pintype "bidirectional"))
    )
    (net (code "77") (name "unconnected-(U1-PR0-Pad20)") (class "Default")
      (node (ref "U1") (pin "20") (pinfunction "PR0_20") (pintype "bidirectional"))
    )
    (net (code "78") (name "unconnected-(USB1-Pad4)") (class "Default")
      (node (ref "USB1") (pin "4") (pinfunction "4_4") (pintype "input"))
    )
  )
)
